# leadtech-arduino-CSPG_concept.net
KiCad netlist of a schematic drawn in EAGLE
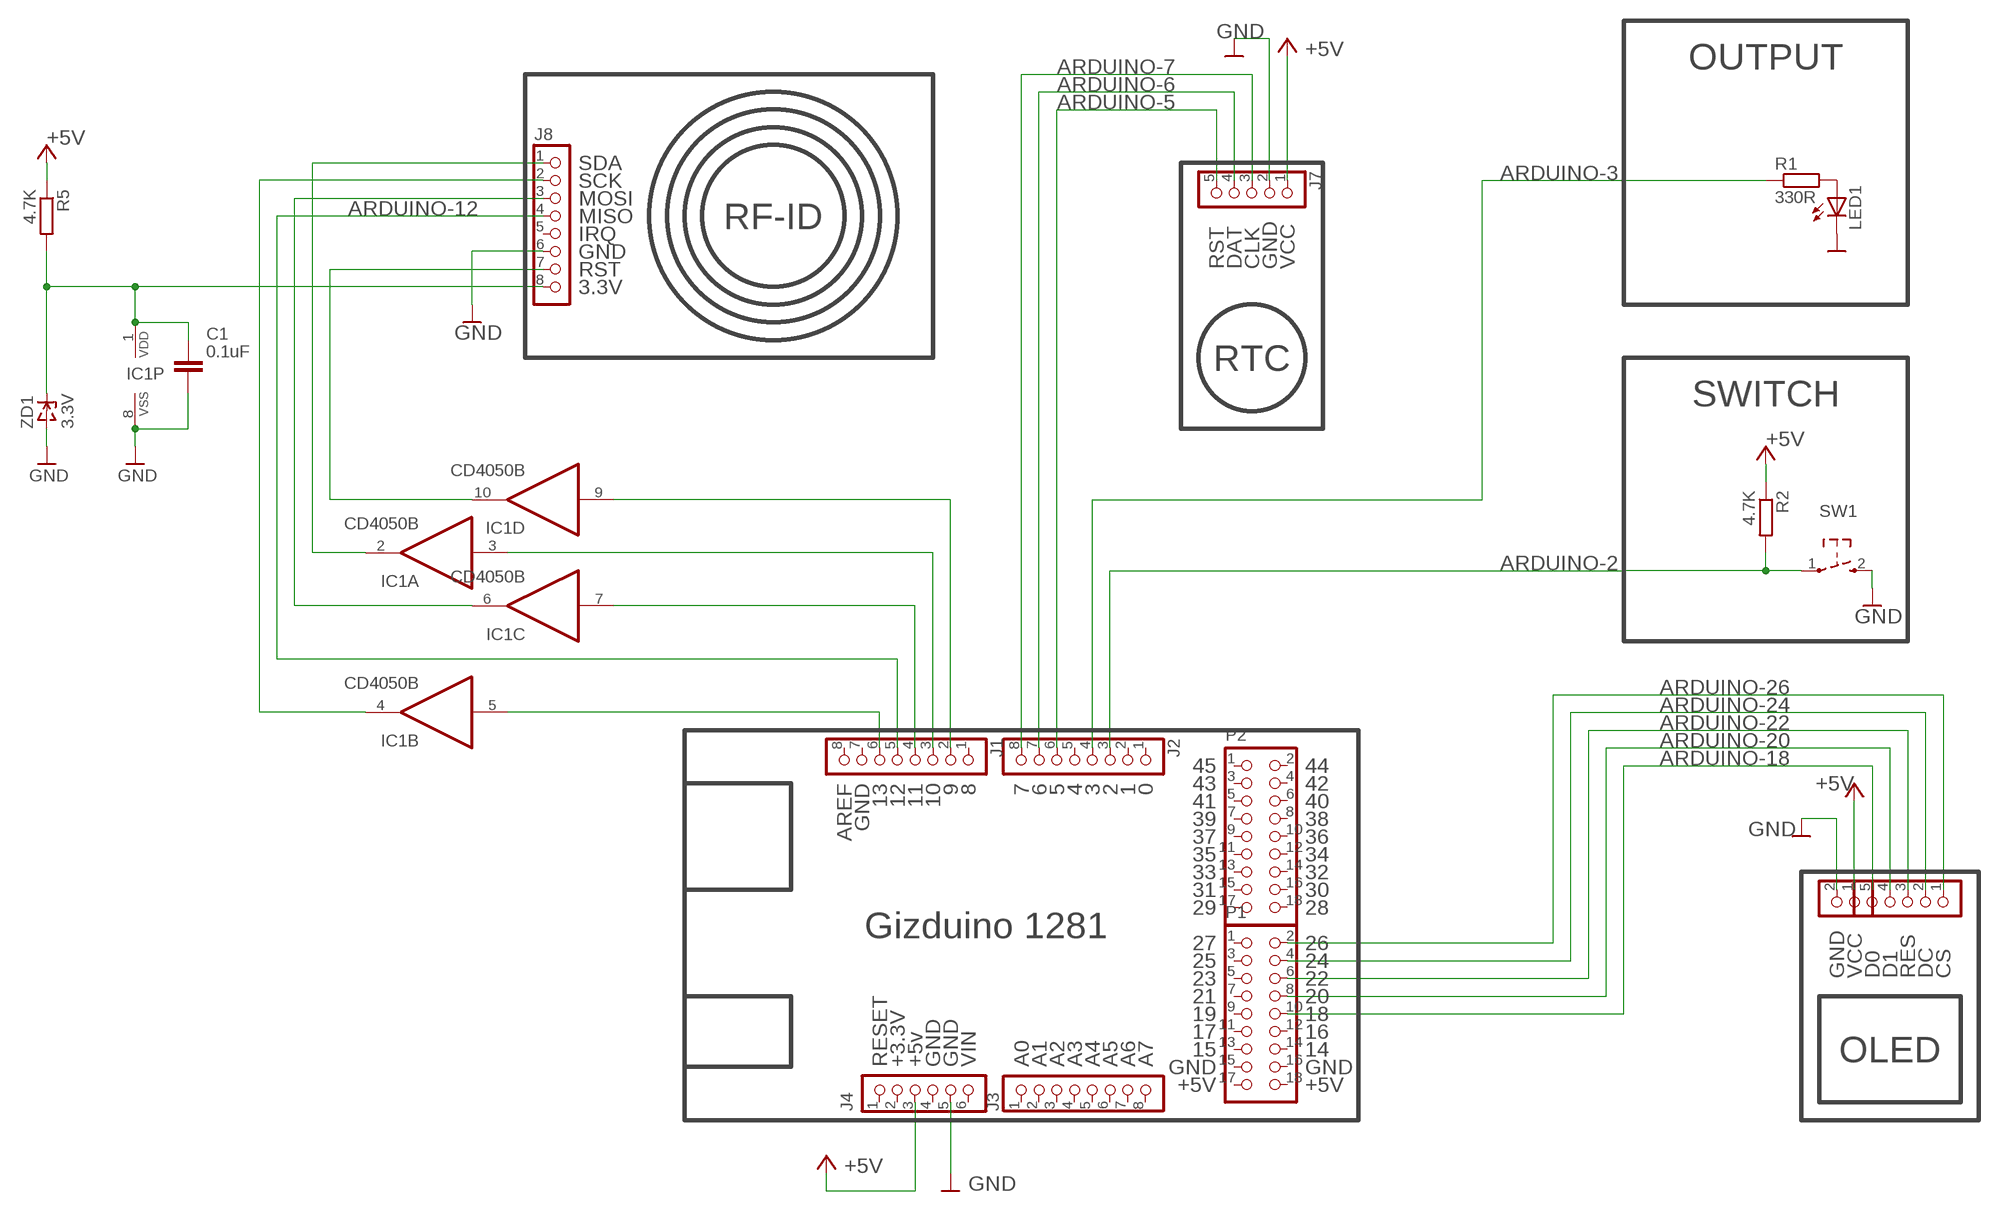
[diagram p0: schematic, sheet 1]

(export (version "E")
  (design (tool "Eeschema 10.0.6"))
  (components
    (comp (ref "C1")
      (value "0.1uF")
      (footprint "eagle-import:C0.1PTH")
      (libsource (lib "eagle-import") (part "CAPACITOR_NPOL-PTH_0.1{dblquote}"))
    )
    (comp (ref "IC1")
      (value "CD4050B")
      (footprint "eagle-import:DIL16")
      (libsource (lib "eagle-import") (part "4050N"))
    )
    (comp (ref "J1")
      (value "CON_HEADER_1X08-PTH")
      (footprint "eagle-import:M1X8")
      (libsource (lib "eagle-import") (part "CON_HEADER_1X08-PTH"))
    )
    (comp (ref "J2")
      (value "CON_HEADER_1X08-PTH")
      (footprint "eagle-import:M1X8")
      (libsource (lib "eagle-import") (part "CON_HEADER_1X08-PTH"))
    )
    (comp (ref "J3")
      (value "CON_HEADER_1X08-PTH")
      (footprint "eagle-import:M1X8")
      (libsource (lib "eagle-import") (part "CON_HEADER_1X08-PTH"))
    )
    (comp (ref "J4")
      (value "CON_HEADER_1X06-PTH")
      (footprint "eagle-import:M1X6")
      (libsource (lib "eagle-import") (part "CON_HEADER_1X06-PTH"))
    )
    (comp (ref "J5")
      (value "CON_HEADER_1X05-PTH")
      (footprint "eagle-import:M1X5")
      (libsource (lib "eagle-import") (part "CON_HEADER_1X05-PTH"))
    )
    (comp (ref "J6")
      (value "CON_HEADER_1X02-PTH")
      (footprint "eagle-import:M1X2")
      (libsource (lib "eagle-import") (part "CON_HEADER_1X02-PTH"))
    )
    (comp (ref "J7")
      (value "CON_HEADER_1X05-PTH")
      (footprint "eagle-import:M1X5")
      (libsource (lib "eagle-import") (part "CON_HEADER_1X05-PTH"))
    )
    (comp (ref "J8")
      (value "CON_HEADER_1X08-PTH")
      (footprint "eagle-import:M1X8")
      (libsource (lib "eagle-import") (part "CON_HEADER_1X08-PTH"))
    )
    (comp (ref "LED1")
      (value "LED-5MM")
      (footprint "eagle-import:LED-5MM")
      (libsource (lib "eagle-import") (part "LED-5MM"))
    )
    (comp (ref "P1")
      (value "CON_HEADER_2X09")
      (footprint "eagle-import:M2X9")
      (libsource (lib "eagle-import") (part "CON_HEADER_2X09"))
    )
    (comp (ref "P2")
      (value "CON_HEADER_2X09")
      (footprint "eagle-import:M2X9")
      (libsource (lib "eagle-import") (part "CON_HEADER_2X09"))
    )
    (comp (ref "R1")
      (value "330R")
      (footprint "eagle-import:R603")
      (libsource (lib "eagle-import") (part "RESISTOR-0603"))
    )
    (comp (ref "R2")
      (value "4.7K")
      (footprint "eagle-import:R603")
      (libsource (lib "eagle-import") (part "RESISTOR-0603"))
    )
    (comp (ref "R5")
      (value "4.7K")
      (footprint "eagle-import:R603")
      (libsource (lib "eagle-import") (part "RESISTOR-0603"))
    )
    (comp (ref "SW1")
      (value "SW_TACT_2P-3X6")
      (footprint "eagle-import:SW_TACT_3X6")
      (libsource (lib "eagle-import") (part "SW_TACT_2P-3X6"))
    )
    (comp (ref "ZD1")
      (value "3.3V")
      (footprint "eagle-import:SOD-123")
      (libsource (lib "eagle-import") (part "ZENERSOD-123"))
    )
  )
  (nets
    (net (code "1") (name "/ARDUINO-2") (class "Default")
      (node (ref "J2") (pin "3") (pinfunction "3_3") (pintype "passive"))
      (node (ref "R2") (pin "2") (pinfunction "2_2") (pintype "passive"))
      (node (ref "SW1") (pin "1") (pinfunction "1_1") (pintype "passive"))
    )
    (net (code "2") (name "/ARDUINO-3") (class "Default")
      (node (ref "J2") (pin "4") (pinfunction "4_4") (pintype "passive"))
      (node (ref "R1") (pin "1") (pinfunction "1_1") (pintype "passive"))
    )
    (net (code "3") (name "/ARDUINO-5") (class "Default")
      (node (ref "J2") (pin "6") (pinfunction "6_6") (pintype "passive"))
      (node (ref "J7") (pin "5") (pinfunction "5_5") (pintype "bidirectional"))
    )
    (net (code "4") (name "/ARDUINO-6") (class "Default")
      (node (ref "J2") (pin "7") (pinfunction "7_7") (pintype "passive"))
      (node (ref "J7") (pin "4") (pinfunction "4_4") (pintype "bidirectional"))
    )
    (net (code "5") (name "/ARDUINO-7") (class "Default")
      (node (ref "J2") (pin "8") (pinfunction "8_8") (pintype "passive"))
      (node (ref "J7") (pin "3") (pinfunction "3_3") (pintype "bidirectional"))
    )
    (net (code "6") (name "/ARDUINO-12") (class "Default")
      (node (ref "J1") (pin "5") (pinfunction "5_5") (pintype "passive"))
      (node (ref "J8") (pin "4") (pinfunction "4_4") (pintype "passive"))
    )
    (net (code "7") (name "/ARDUINO-18") (class "Default")
      (node (ref "J5") (pin "5") (pinfunction "5_5") (pintype "bidirectional"))
      (node (ref "P1") (pin "10") (pinfunction "10_10") (pintype "passive"))
    )
    (net (code "8") (name "/ARDUINO-20") (class "Default")
      (node (ref "J5") (pin "4") (pinfunction "4_4") (pintype "bidirectional"))
      (node (ref "P1") (pin "8") (pinfunction "8_8") (pintype "passive"))
    )
    (net (code "9") (name "/ARDUINO-22") (class "Default")
      (node (ref "J5") (pin "3") (pinfunction "3_3") (pintype "bidirectional"))
      (node (ref "P1") (pin "6") (pinfunction "6_6") (pintype "passive"))
    )
    (net (code "10") (name "/ARDUINO-24") (class "Default")
      (node (ref "J5") (pin "2") (pinfunction "2_2") (pintype "bidirectional"))
      (node (ref "P1") (pin "4") (pinfunction "4_4") (pintype "passive"))
    )
    (net (code "11") (name "/ARDUINO-26") (class "Default")
      (node (ref "J5") (pin "1") (pinfunction "1_1") (pintype "bidirectional"))
      (node (ref "P1") (pin "2") (pinfunction "2_2") (pintype "passive"))
    )
    (net (code "12") (name "Net-(IC1A-I)") (class "Default")
      (node (ref "IC1") (pin "3") (pinfunction "I_3") (pintype "input"))
      (node (ref "J1") (pin "3") (pinfunction "3_3") (pintype "passive"))
    )
    (net (code "13") (name "Net-(IC1A-O)") (class "Default")
      (node (ref "IC1") (pin "2") (pinfunction "O_2") (pintype "output"))
      (node (ref "J8") (pin "1") (pinfunction "1_1") (pintype "passive"))
    )
    (net (code "14") (name "Net-(IC1B-I)") (class "Default")
      (node (ref "IC1") (pin "5") (pinfunction "I_5") (pintype "input"))
      (node (ref "J1") (pin "6") (pinfunction "6_6") (pintype "passive"))
    )
    (net (code "15") (name "Net-(IC1B-O)") (class "Default")
      (node (ref "IC1") (pin "4") (pinfunction "O_4") (pintype "output"))
      (node (ref "J8") (pin "2") (pinfunction "2_2") (pintype "passive"))
    )
    (net (code "16") (name "Net-(IC1C-I)") (class "Default")
      (node (ref "IC1") (pin "7") (pinfunction "I_7") (pintype "input"))
      (node (ref "J1") (pin "4") (pinfunction "4_4") (pintype "passive"))
    )
    (net (code "17") (name "Net-(IC1C-O)") (class "Default")
      (node (ref "IC1") (pin "6") (pinfunction "O_6") (pintype "output"))
      (node (ref "J8") (pin "3") (pinfunction "3_3") (pintype "passive"))
    )
    (net (code "18") (name "Net-(IC1D-I)") (class "Default")
      (node (ref "IC1") (pin "9") (pinfunction "I_9") (pintype "input"))
      (node (ref "J1") (pin "2") (pinfunction "2_2") (pintype "passive"))
    )
    (net (code "19") (name "Net-(IC1D-O)") (class "Default")
      (node (ref "IC1") (pin "10") (pinfunction "O_10") (pintype "output"))
      (node (ref "J8") (pin "7") (pinfunction "7_7") (pintype "passive"))
    )
    (net (code "20") (name "Net-(IC1G-VDD)") (class "Default")
      (node (ref "C1") (pin "1") (pinfunction "1_1") (pintype "passive"))
      (node (ref "IC1") (pin "1") (pinfunction "VDD_1") (pintype "power_in"))
      (node (ref "J8") (pin "8") (pinfunction "8_8") (pintype "passive"))
      (node (ref "R5") (pin "2") (pinfunction "2_2") (pintype "passive"))
      (node (ref "ZD1") (pin "C") (pinfunction "C_C") (pintype "passive"))
    )
    (net (code "21") (name "Net-(LED1-PadA)") (class "Default")
      (node (ref "LED1") (pin "A") (pinfunction "A_A") (pintype "passive"))
      (node (ref "R1") (pin "2") (pinfunction "2_2") (pintype "passive"))
    )
    (net (code "22") (name "SUPPLY_+5V") (class "Default")
      (node (ref "J4") (pin "3") (pinfunction "3_3") (pintype "passive"))
      (node (ref "J6") (pin "1") (pinfunction "1_1") (pintype "passive"))
      (node (ref "J7") (pin "1") (pinfunction "1_1") (pintype "bidirectional"))
      (node (ref "R2") (pin "1") (pinfunction "1_1") (pintype "passive"))
      (node (ref "R5") (pin "1") (pinfunction "1_1") (pintype "passive"))
    )
    (net (code "23") (name "SUPPLY_GND") (class "Default")
      (node (ref "C1") (pin "2") (pinfunction "2_2") (pintype "passive"))
      (node (ref "IC1") (pin "8") (pinfunction "VSS_8") (pintype "power_in"))
      (node (ref "J4") (pin "5") (pinfunction "5_5") (pintype "passive"))
      (node (ref "J6") (pin "2") (pinfunction "2_2") (pintype "passive"))
      (node (ref "J7") (pin "2") (pinfunction "2_2") (pintype "bidirectional"))
      (node (ref "J8") (pin "6") (pinfunction "6_6") (pintype "passive"))
      (node (ref "LED1") (pin "K") (pinfunction "C_K") (pintype "passive"))
      (node (ref "SW1") (pin "2") (pinfunction "3_2") (pintype "passive"))
      (node (ref "ZD1") (pin "A") (pinfunction "A_A") (pintype "passive"))
    )
    (net (code "24") (name "unconnected-(J1-Pad1)") (class "Default")
      (node (ref "J1") (pin "1") (pinfunction "1_1") (pintype "passive"))
    )
    (net (code "25") (name "unconnected-(J1-Pad7)") (class "Default")
      (node (ref "J1") (pin "7") (pinfunction "7_7") (pintype "passive"))
    )
    (net (code "26") (name "unconnected-(J1-Pad8)") (class "Default")
      (node (ref "J1") (pin "8") (pinfunction "8_8") (pintype "passive"))
    )
    (net (code "27") (name "unconnected-(J2-Pad1)") (class "Default")
      (node (ref "J2") (pin "1") (pinfunction "1_1") (pintype "passive"))
    )
    (net (code "28") (name "unconnected-(J2-Pad2)") (class "Default")
      (node (ref "J2") (pin "2") (pinfunction "2_2") (pintype "passive"))
    )
    (net (code "29") (name "unconnected-(J2-Pad5)") (class "Default")
      (node (ref "J2") (pin "5") (pinfunction "5_5") (pintype "passive"))
    )
    (net (code "30") (name "unconnected-(J3-Pad1)") (class "Default")
      (node (ref "J3") (pin "1") (pinfunction "1_1") (pintype "passive"))
    )
    (net (code "31") (name "unconnected-(J3-Pad2)") (class "Default")
      (node (ref "J3") (pin "2") (pinfunction "2_2") (pintype "passive"))
    )
    (net (code "32") (name "unconnected-(J3-Pad3)") (class "Default")
      (node (ref "J3") (pin "3") (pinfunction "3_3") (pintype "passive"))
    )
    (net (code "33") (name "unconnected-(J3-Pad4)") (class "Default")
      (node (ref "J3") (pin "4") (pinfunction "4_4") (pintype "passive"))
    )
    (net (code "34") (name "unconnected-(J3-Pad5)") (class "Default")
      (node (ref "J3") (pin "5") (pinfunction "5_5") (pintype "passive"))
    )
    (net (code "35") (name "unconnected-(J3-Pad6)") (class "Default")
      (node (ref "J3") (pin "6") (pinfunction "6_6") (pintype "passive"))
    )
    (net (code "36") (name "unconnected-(J3-Pad7)") (class "Default")
      (node (ref "J3") (pin "7") (pinfunction "7_7") (pintype "passive"))
    )
    (net (code "37") (name "unconnected-(J3-Pad8)") (class "Default")
      (node (ref "J3") (pin "8") (pinfunction "8_8") (pintype "passive"))
    )
    (net (code "38") (name "unconnected-(J4-Pad1)") (class "Default")
      (node (ref "J4") (pin "1") (pinfunction "1_1") (pintype "bidirectional"))
    )
    (net (code "39") (name "unconnected-(J4-Pad2)") (class "Default")
      (node (ref "J4") (pin "2") (pinfunction "2_2") (pintype "bidirectional"))
    )
    (net (code "40") (name "unconnected-(J4-Pad4)") (class "Default")
      (node (ref "J4") (pin "4") (pinfunction "4_4") (pintype "passive"))
    )
    (net (code "41") (name "unconnected-(J4-Pad6)") (class "Default")
      (node (ref "J4") (pin "6") (pinfunction "6_6") (pintype "passive"))
    )
    (net (code "42") (name "unconnected-(J8-Pad5)") (class "Default")
      (node (ref "J8") (pin "5") (pinfunction "5_5") (pintype "passive"))
    )
    (net (code "43") (name "unconnected-(P1-Pad1)") (class "Default")
      (node (ref "P1") (pin "1") (pinfunction "1_1") (pintype "passive"))
    )
    (net (code "44") (name "unconnected-(P1-Pad3)") (class "Default")
      (node (ref "P1") (pin "3") (pinfunction "3_3") (pintype "passive"))
    )
    (net (code "45") (name "unconnected-(P1-Pad5)") (class "Default")
      (node (ref "P1") (pin "5") (pinfunction "5_5") (pintype "passive"))
    )
    (net (code "46") (name "unconnected-(P1-Pad7)") (class "Default")
      (node (ref "P1") (pin "7") (pinfunction "7_7") (pintype "passive"))
    )
    (net (code "47") (name "unconnected-(P1-Pad9)") (class "Default")
      (node (ref "P1") (pin "9") (pinfunction "9_9") (pintype "passive"))
    )
    (net (code "48") (name "unconnected-(P1-Pad11)") (class "Default")
      (node (ref "P1") (pin "11") (pinfunction "11_11") (pintype "passive"))
    )
    (net (code "49") (name "unconnected-(P1-Pad12)") (class "Default")
      (node (ref "P1") (pin "12") (pinfunction "12_12") (pintype "passive"))
    )
    (net (code "50") (name "unconnected-(P1-Pad13)") (class "Default")
      (node (ref "P1") (pin "13") (pinfunction "13_13") (pintype "passive"))
    )
    (net (code "51") (name "unconnected-(P1-Pad14)") (class "Default")
      (node (ref "P1") (pin "14") (pinfunction "14_14") (pintype "passive"))
    )
    (net (code "52") (name "unconnected-(P1-Pad15)") (class "Default")
      (node (ref "P1") (pin "15") (pinfunction "15_15") (pintype "passive"))
    )
    (net (code "53") (name "unconnected-(P1-Pad16)") (class "Default")
      (node (ref "P1") (pin "16") (pinfunction "16_16") (pintype "passive"))
    )
    (net (code "54") (name "unconnected-(P1-Pad17)") (class "Default")
      (node (ref "P1") (pin "17") (pinfunction "17_17") (pintype "passive"))
    )
    (net (code "55") (name "unconnected-(P1-Pad18)") (class "Default")
      (node (ref "P1") (pin "18") (pinfunction "18_18") (pintype "passive"))
    )
    (net (code "56") (name "unconnected-(P2-Pad1)") (class "Default")
      (node (ref "P2") (pin "1") (pinfunction "1_1") (pintype "passive"))
    )
    (net (code "57") (name "unconnected-(P2-Pad2)") (class "Default")
      (node (ref "P2") (pin "2") (pinfunction "2_2") (pintype "passive"))
    )
    (net (code "58") (name "unconnected-(P2-Pad3)") (class "Default")
      (node (ref "P2") (pin "3") (pinfunction "3_3") (pintype "passive"))
    )
    (net (code "59") (name "unconnected-(P2-Pad4)") (class "Default")
      (node (ref "P2") (pin "4") (pinfunction "4_4") (pintype "passive"))
    )
    (net (code "60") (name "unconnected-(P2-Pad5)") (class "Default")
      (node (ref "P2") (pin "5") (pinfunction "5_5") (pintype "passive"))
    )
    (net (code "61") (name "unconnected-(P2-Pad6)") (class "Default")
      (node (ref "P2") (pin "6") (pinfunction "6_6") (pintype "passive"))
    )
    (net (code "62") (name "unconnected-(P2-Pad7)") (class "Default")
      (node (ref "P2") (pin "7") (pinfunction "7_7") (pintype "passive"))
    )
    (net (code "63") (name "unconnected-(P2-Pad8)") (class "Default")
      (node (ref "P2") (pin "8") (pinfunction "8_8") (pintype "passive"))
    )
    (net (code "64") (name "unconnected-(P2-Pad9)") (class "Default")
      (node (ref "P2") (pin "9") (pinfunction "9_9") (pintype "passive"))
    )
    (net (code "65") (name "unconnected-(P2-Pad10)") (class "Default")
      (node (ref "P2") (pin "10") (pinfunction "10_10") (pintype "passive"))
    )
    (net (code "66") (name "unconnected-(P2-Pad11)") (class "Default")
      (node (ref "P2") (pin "11") (pinfunction "11_11") (pintype "passive"))
    )
    (net (code "67") (name "unconnected-(P2-Pad12)") (class "Default")
      (node (ref "P2") (pin "12") (pinfunction "12_12") (pintype "passive"))
    )
    (net (code "68") (name "unconnected-(P2-Pad13)") (class "Default")
      (node (ref "P2") (pin "13") (pinfunction "13_13") (pintype "passive"))
    )
    (net (code "69") (name "unconnected-(P2-Pad14)") (class "Default")
      (node (ref "P2") (pin "14") (pinfunction "14_14") (pintype "passive"))
    )
    (net (code "70") (name "unconnected-(P2-Pad15)") (class "Default")
      (node (ref "P2") (pin "15") (pinfunction "15_15") (pintype "passive"))
    )
    (net (code "71") (name "unconnected-(P2-Pad16)") (class "Default")
      (node (ref "P2") (pin "16") (pinfunction "16_16") (pintype "passive"))
    )
    (net (code "72") (name "unconnected-(P2-Pad17)") (class "Default")
      (node (ref "P2") (pin "17") (pinfunction "17_17") (pintype "passive"))
    )
    (net (code "73") (name "unconnected-(P2-Pad18)") (class "Default")
      (node (ref "P2") (pin "18") (pinfunction "18_18") (pintype "passive"))
    )
  )
)
